# usomiq.net
KiCad netlist of a schematic drawn in Altium Designer
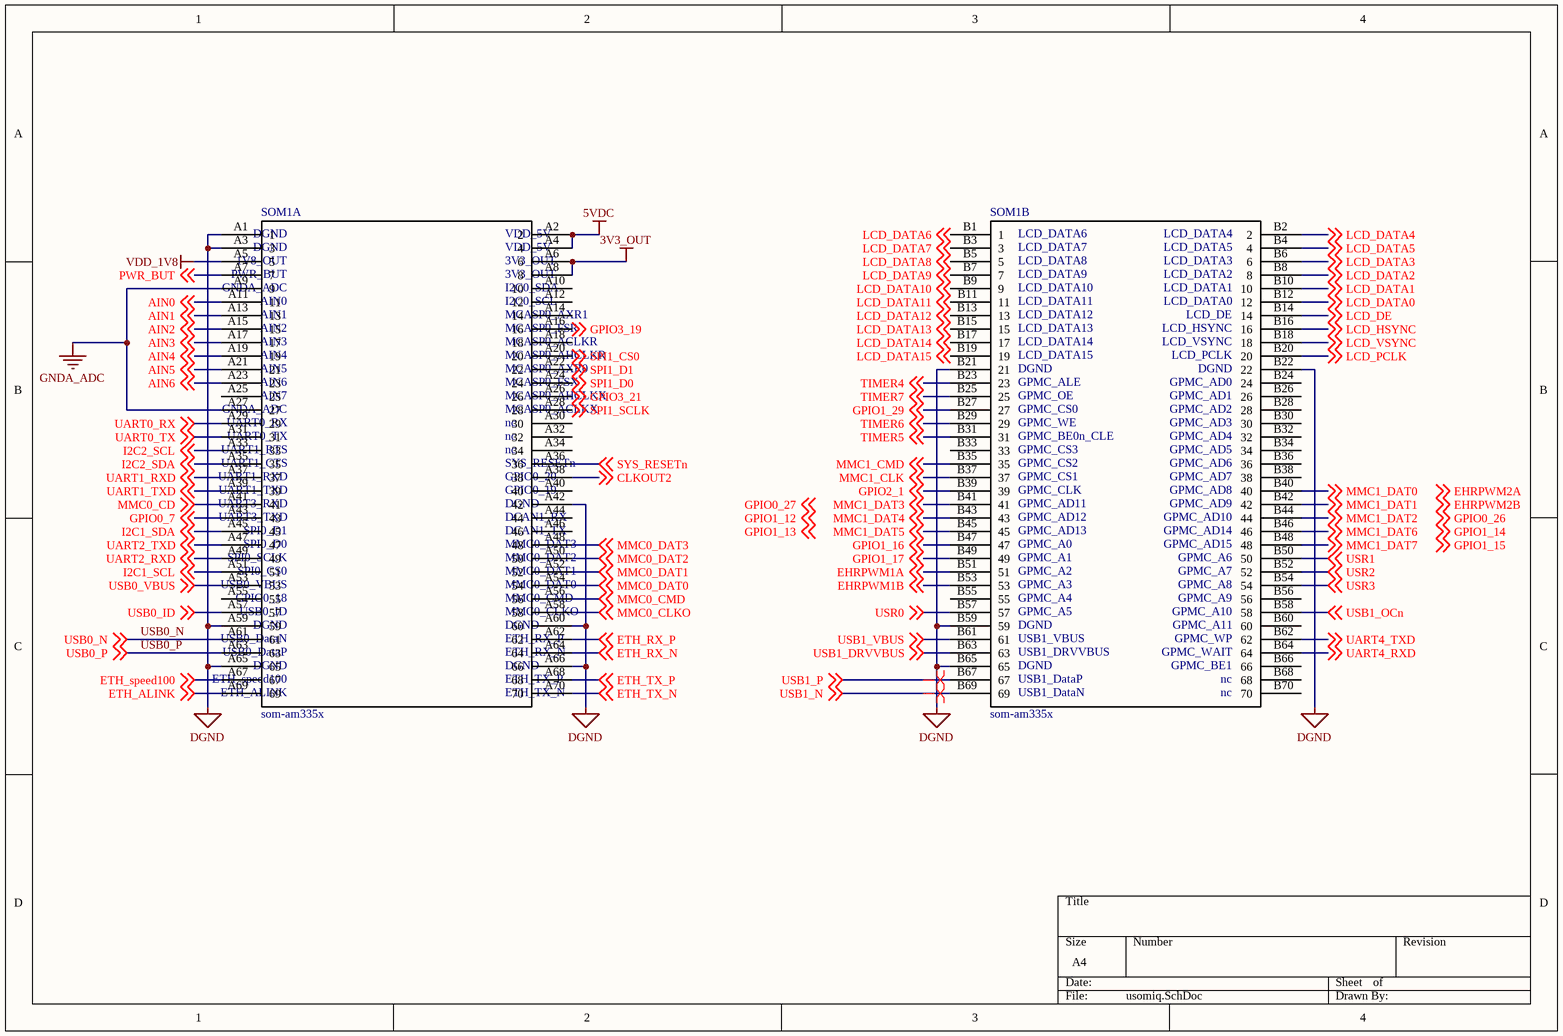
[diagram p0: usomiq.SchDoc]

(export (version "E")
  (design (tool "Eeschema 10.0.6"))
  (components
    (comp (ref "SOM1")
      (value "som-am335x")
      (footprint "am3359_module-sockets")
      (libsource (lib "usomiq-base") (part "som-am335x"))
    )
  )
  (nets
    (net (code "1") (name "3V3_OUT") (class "Default")
      (node (ref "SOM1") (pin "A6") (pinfunction "6_A6") (pintype "passive"))
      (node (ref "SOM1") (pin "A8") (pinfunction "8_A8") (pintype "passive"))
    )
    (net (code "2") (name "5VDC") (class "Default")
      (node (ref "SOM1") (pin "A2") (pinfunction "2_A2") (pintype "passive"))
      (node (ref "SOM1") (pin "A4") (pinfunction "4_A4") (pintype "passive"))
    )
    (net (code "3") (name "AIN0") (class "Default")
      (node (ref "SOM1") (pin "A11") (pinfunction "11_A11") (pintype "passive"))
    )
    (net (code "4") (name "AIN1") (class "Default")
      (node (ref "SOM1") (pin "A13") (pinfunction "13_A13") (pintype "passive"))
    )
    (net (code "5") (name "AIN2") (class "Default")
      (node (ref "SOM1") (pin "A15") (pinfunction "15_A15") (pintype "passive"))
    )
    (net (code "6") (name "AIN3") (class "Default")
      (node (ref "SOM1") (pin "A17") (pinfunction "17_A17") (pintype "passive"))
    )
    (net (code "7") (name "AIN4") (class "Default")
      (node (ref "SOM1") (pin "A19") (pinfunction "19_A19") (pintype "passive"))
    )
    (net (code "8") (name "AIN5") (class "Default")
      (node (ref "SOM1") (pin "A21") (pinfunction "21_A21") (pintype "passive"))
    )
    (net (code "9") (name "AIN6") (class "Default")
      (node (ref "SOM1") (pin "A23") (pinfunction "23_A23") (pintype "passive"))
    )
    (net (code "10") (name "CLKOUT2") (class "Default")
      (node (ref "SOM1") (pin "A38") (pinfunction "38_A38") (pintype "passive"))
    )
    (net (code "11") (name "DGND") (class "Default")
      (node (ref "SOM1") (pin "A1") (pinfunction "1_A1") (pintype "passive"))
      (node (ref "SOM1") (pin "A3") (pinfunction "3_A3") (pintype "passive"))
      (node (ref "SOM1") (pin "A42") (pinfunction "42_A42") (pintype "passive"))
      (node (ref "SOM1") (pin "A59") (pinfunction "59_A59") (pintype "passive"))
      (node (ref "SOM1") (pin "A60") (pinfunction "60_A60") (pintype "passive"))
      (node (ref "SOM1") (pin "A65") (pinfunction "65_A65") (pintype "passive"))
      (node (ref "SOM1") (pin "A66") (pinfunction "66_A66") (pintype "passive"))
      (node (ref "SOM1") (pin "B21") (pinfunction "21_B21") (pintype "passive"))
      (node (ref "SOM1") (pin "B22") (pinfunction "22_B22") (pintype "passive"))
      (node (ref "SOM1") (pin "B59") (pinfunction "59_B59") (pintype "passive"))
      (node (ref "SOM1") (pin "B65") (pinfunction "65_B65") (pintype "passive"))
    )
    (net (code "12") (name "EHRPWM1A") (class "Default")
      (node (ref "SOM1") (pin "B51") (pinfunction "51_B51") (pintype "passive"))
    )
    (net (code "13") (name "EHRPWM1B") (class "Default")
      (node (ref "SOM1") (pin "B53") (pinfunction "53_B53") (pintype "passive"))
    )
    (net (code "16") (name "ETH_ALINK") (class "Default")
      (node (ref "SOM1") (pin "A69") (pinfunction "69_A69") (pintype "passive"))
    )
    (net (code "17") (name "ETH_RX_N") (class "Default")
      (node (ref "SOM1") (pin "A64") (pinfunction "64_A64") (pintype "passive"))
    )
    (net (code "18") (name "ETH_RX_P") (class "Default")
      (node (ref "SOM1") (pin "A62") (pinfunction "62_A62") (pintype "passive"))
    )
    (net (code "19") (name "ETH_TX_N") (class "Default")
      (node (ref "SOM1") (pin "A70") (pinfunction "70_A70") (pintype "passive"))
    )
    (net (code "20") (name "ETH_TX_P") (class "Default")
      (node (ref "SOM1") (pin "A68") (pinfunction "68_A68") (pintype "passive"))
    )
    (net (code "21") (name "ETH_speed100") (class "Default")
      (node (ref "SOM1") (pin "A67") (pinfunction "67_A67") (pintype "passive"))
    )
    (net (code "22") (name "GNDA_ADC") (class "Default")
      (node (ref "SOM1") (pin "A27") (pinfunction "27_A27") (pintype "passive"))
      (node (ref "SOM1") (pin "A9") (pinfunction "9_A9") (pintype "passive"))
    )
    (net (code "23") (name "GPIO0_7") (class "Default")
      (node (ref "SOM1") (pin "A43") (pinfunction "43_A43") (pintype "passive"))
    )
    (net (code "30") (name "GPIO1_16") (class "Default")
      (node (ref "SOM1") (pin "B47") (pinfunction "47_B47") (pintype "passive"))
    )
    (net (code "31") (name "GPIO1_17") (class "Default")
      (node (ref "SOM1") (pin "B49") (pinfunction "49_B49") (pintype "passive"))
    )
    (net (code "32") (name "GPIO1_29") (class "Default")
      (node (ref "SOM1") (pin "B27") (pinfunction "27_B27") (pintype "passive"))
    )
    (net (code "33") (name "GPIO2_1") (class "Default")
      (node (ref "SOM1") (pin "B39") (pinfunction "39_B39") (pintype "passive"))
    )
    (net (code "34") (name "GPIO3_19") (class "Default")
      (node (ref "SOM1") (pin "A16") (pinfunction "16_A16") (pintype "passive"))
    )
    (net (code "35") (name "GPIO3_21") (class "Default")
      (node (ref "SOM1") (pin "A26") (pinfunction "26_A26") (pintype "passive"))
    )
    (net (code "36") (name "I2C1_SCL") (class "Default")
      (node (ref "SOM1") (pin "A51") (pinfunction "51_A51") (pintype "passive"))
    )
    (net (code "37") (name "I2C1_SDA") (class "Default")
      (node (ref "SOM1") (pin "A45") (pinfunction "45_A45") (pintype "passive"))
    )
    (net (code "38") (name "I2C2_SCL") (class "Default")
      (node (ref "SOM1") (pin "A33") (pinfunction "33_A33") (pintype "passive"))
    )
    (net (code "39") (name "I2C2_SDA") (class "Default")
      (node (ref "SOM1") (pin "A35") (pinfunction "35_A35") (pintype "passive"))
    )
    (net (code "40") (name "LCD_DATA0") (class "Default")
      (node (ref "SOM1") (pin "B12") (pinfunction "12_B12") (pintype "passive"))
    )
    (net (code "41") (name "LCD_DATA1") (class "Default")
      (node (ref "SOM1") (pin "B10") (pinfunction "10_B10") (pintype "passive"))
    )
    (net (code "42") (name "LCD_DATA2") (class "Default")
      (node (ref "SOM1") (pin "B8") (pinfunction "8_B8") (pintype "passive"))
    )
    (net (code "43") (name "LCD_DATA3") (class "Default")
      (node (ref "SOM1") (pin "B6") (pinfunction "6_B6") (pintype "passive"))
    )
    (net (code "44") (name "LCD_DATA4") (class "Default")
      (node (ref "SOM1") (pin "B2") (pinfunction "2_B2") (pintype "passive"))
    )
    (net (code "45") (name "LCD_DATA5") (class "Default")
      (node (ref "SOM1") (pin "B4") (pinfunction "4_B4") (pintype "passive"))
    )
    (net (code "46") (name "LCD_DATA6") (class "Default")
      (node (ref "SOM1") (pin "B1") (pinfunction "1_B1") (pintype "passive"))
    )
    (net (code "47") (name "LCD_DATA7") (class "Default")
      (node (ref "SOM1") (pin "B3") (pinfunction "3_B3") (pintype "passive"))
    )
    (net (code "48") (name "LCD_DATA8") (class "Default")
      (node (ref "SOM1") (pin "B5") (pinfunction "5_B5") (pintype "passive"))
    )
    (net (code "49") (name "LCD_DATA9") (class "Default")
      (node (ref "SOM1") (pin "B7") (pinfunction "7_B7") (pintype "passive"))
    )
    (net (code "50") (name "LCD_DATA10") (class "Default")
      (node (ref "SOM1") (pin "B9") (pinfunction "9_B9") (pintype "passive"))
    )
    (net (code "51") (name "LCD_DATA11") (class "Default")
      (node (ref "SOM1") (pin "B11") (pinfunction "11_B11") (pintype "passive"))
    )
    (net (code "52") (name "LCD_DATA12") (class "Default")
      (node (ref "SOM1") (pin "B13") (pinfunction "13_B13") (pintype "passive"))
    )
    (net (code "53") (name "LCD_DATA13") (class "Default")
      (node (ref "SOM1") (pin "B15") (pinfunction "15_B15") (pintype "passive"))
    )
    (net (code "54") (name "LCD_DATA14") (class "Default")
      (node (ref "SOM1") (pin "B17") (pinfunction "17_B17") (pintype "passive"))
    )
    (net (code "55") (name "LCD_DATA15") (class "Default")
      (node (ref "SOM1") (pin "B19") (pinfunction "19_B19") (pintype "passive"))
    )
    (net (code "56") (name "LCD_DE") (class "Default")
      (node (ref "SOM1") (pin "B14") (pinfunction "14_B14") (pintype "passive"))
    )
    (net (code "57") (name "LCD_HSYNC") (class "Default")
      (node (ref "SOM1") (pin "B16") (pinfunction "16_B16") (pintype "passive"))
    )
    (net (code "58") (name "LCD_PCLK") (class "Default")
      (node (ref "SOM1") (pin "B20") (pinfunction "20_B20") (pintype "passive"))
    )
    (net (code "59") (name "LCD_VSYNC") (class "Default")
      (node (ref "SOM1") (pin "B18") (pinfunction "18_B18") (pintype "passive"))
    )
    (net (code "60") (name "MMC0_CD") (class "Default")
      (node (ref "SOM1") (pin "A41") (pinfunction "41_A41") (pintype "passive"))
    )
    (net (code "61") (name "MMC0_CLKO") (class "Default")
      (node (ref "SOM1") (pin "A58") (pinfunction "58_A58") (pintype "passive"))
    )
    (net (code "62") (name "MMC0_CMD") (class "Default")
      (node (ref "SOM1") (pin "A56") (pinfunction "56_A56") (pintype "passive"))
    )
    (net (code "63") (name "MMC0_DAT0") (class "Default")
      (node (ref "SOM1") (pin "A54") (pinfunction "54_A54") (pintype "passive"))
    )
    (net (code "64") (name "MMC0_DAT1") (class "Default")
      (node (ref "SOM1") (pin "A52") (pinfunction "52_A52") (pintype "passive"))
    )
    (net (code "65") (name "MMC0_DAT2") (class "Default")
      (node (ref "SOM1") (pin "A50") (pinfunction "50_A50") (pintype "passive"))
    )
    (net (code "66") (name "MMC0_DAT3") (class "Default")
      (node (ref "SOM1") (pin "A48") (pinfunction "48_A48") (pintype "passive"))
    )
    (net (code "67") (name "MMC1_CLK") (class "Default")
      (node (ref "SOM1") (pin "B37") (pinfunction "37_B37") (pintype "passive"))
    )
    (net (code "68") (name "MMC1_CMD") (class "Default")
      (node (ref "SOM1") (pin "B35") (pinfunction "35_B35") (pintype "passive"))
    )
    (net (code "69") (name "MMC1_DAT0") (class "Default")
      (node (ref "SOM1") (pin "B40") (pinfunction "40_B40") (pintype "passive"))
    )
    (net (code "70") (name "MMC1_DAT1") (class "Default")
      (node (ref "SOM1") (pin "B42") (pinfunction "42_B42") (pintype "passive"))
    )
    (net (code "71") (name "MMC1_DAT2") (class "Default")
      (node (ref "SOM1") (pin "B44") (pinfunction "44_B44") (pintype "passive"))
    )
    (net (code "72") (name "MMC1_DAT3") (class "Default")
      (node (ref "SOM1") (pin "B41") (pinfunction "41_B41") (pintype "passive"))
    )
    (net (code "73") (name "MMC1_DAT4") (class "Default")
      (node (ref "SOM1") (pin "B43") (pinfunction "43_B43") (pintype "passive"))
    )
    (net (code "74") (name "MMC1_DAT5") (class "Default")
      (node (ref "SOM1") (pin "B45") (pinfunction "45_B45") (pintype "passive"))
    )
    (net (code "75") (name "MMC1_DAT6") (class "Default")
      (node (ref "SOM1") (pin "B46") (pinfunction "46_B46") (pintype "passive"))
    )
    (net (code "76") (name "MMC1_DAT7") (class "Default")
      (node (ref "SOM1") (pin "B48") (pinfunction "48_B48") (pintype "passive"))
    )
    (net (code "77") (name "PWR_BUT") (class "Default")
      (node (ref "SOM1") (pin "A7") (pinfunction "7_A7") (pintype "passive"))
    )
    (net (code "78") (name "SPI1_CS0") (class "Default")
      (node (ref "SOM1") (pin "A20") (pinfunction "20_A20") (pintype "passive"))
    )
    (net (code "79") (name "SPI1_D0") (class "Default")
      (node (ref "SOM1") (pin "A24") (pinfunction "24_A24") (pintype "passive"))
    )
    (net (code "80") (name "SPI1_D1") (class "Default")
      (node (ref "SOM1") (pin "A22") (pinfunction "22_A22") (pintype "passive"))
    )
    (net (code "81") (name "SPI1_SCLK") (class "Default")
      (node (ref "SOM1") (pin "A28") (pinfunction "28_A28") (pintype "passive"))
    )
    (net (code "82") (name "SYS_RESETn") (class "Default")
      (node (ref "SOM1") (pin "A36") (pinfunction "36_A36") (pintype "passive"))
    )
    (net (code "83") (name "TIMER4") (class "Default")
      (node (ref "SOM1") (pin "B23") (pinfunction "23_B23") (pintype "passive"))
    )
    (net (code "84") (name "TIMER5") (class "Default")
      (node (ref "SOM1") (pin "B31") (pinfunction "31_B31") (pintype "passive"))
    )
    (net (code "85") (name "TIMER6") (class "Default")
      (node (ref "SOM1") (pin "B29") (pinfunction "29_B29") (pintype "passive"))
    )
    (net (code "86") (name "TIMER7") (class "Default")
      (node (ref "SOM1") (pin "B25") (pinfunction "25_B25") (pintype "passive"))
    )
    (net (code "87") (name "UART0_RX") (class "Default")
      (node (ref "SOM1") (pin "A29") (pinfunction "29_A29") (pintype "passive"))
    )
    (net (code "88") (name "UART0_TX") (class "Default")
      (node (ref "SOM1") (pin "A31") (pinfunction "31_A31") (pintype "passive"))
    )
    (net (code "89") (name "UART1_RXD") (class "Default")
      (node (ref "SOM1") (pin "A37") (pinfunction "37_A37") (pintype "passive"))
    )
    (net (code "90") (name "UART1_TXD") (class "Default")
      (node (ref "SOM1") (pin "A39") (pinfunction "39_A39") (pintype "passive"))
    )
    (net (code "91") (name "UART2_RXD") (class "Default")
      (node (ref "SOM1") (pin "A49") (pinfunction "49_A49") (pintype "passive"))
    )
    (net (code "92") (name "UART2_TXD") (class "Default")
      (node (ref "SOM1") (pin "A47") (pinfunction "47_A47") (pintype "passive"))
    )
    (net (code "93") (name "UART4_RXD") (class "Default")
      (node (ref "SOM1") (pin "B64") (pinfunction "64_B64") (pintype "passive"))
    )
    (net (code "94") (name "UART4_TXD") (class "Default")
      (node (ref "SOM1") (pin "B62") (pinfunction "62_B62") (pintype "passive"))
    )
    (net (code "95") (name "USB0_ID") (class "Default")
      (node (ref "SOM1") (pin "A57") (pinfunction "57_A57") (pintype "passive"))
    )
    (net (code "96") (name "USB0_N") (class "Default")
      (node (ref "SOM1") (pin "A61") (pinfunction "61_A61") (pintype "passive"))
    )
    (net (code "97") (name "USB0_P") (class "Default")
      (node (ref "SOM1") (pin "A63") (pinfunction "63_A63") (pintype "passive"))
    )
    (net (code "98") (name "USB0_VBUS") (class "Default")
      (node (ref "SOM1") (pin "A53") (pinfunction "53_A53") (pintype "passive"))
    )
    (net (code "99") (name "USB1_DRVVBUS") (class "Default")
      (node (ref "SOM1") (pin "B63") (pinfunction "63_B63") (pintype "passive"))
    )
    (net (code "100") (name "USB1_N") (class "Default")
      (node (ref "SOM1") (pin "B69") (pinfunction "69_B69") (pintype "passive"))
    )
    (net (code "101") (name "USB1_OCn") (class "Default")
      (node (ref "SOM1") (pin "B58") (pinfunction "58_B58") (pintype "passive"))
    )
    (net (code "102") (name "USB1_P") (class "Default")
      (node (ref "SOM1") (pin "B67") (pinfunction "67_B67") (pintype "passive"))
    )
    (net (code "103") (name "USB1_VBUS") (class "Default")
      (node (ref "SOM1") (pin "B61") (pinfunction "61_B61") (pintype "passive"))
    )
    (net (code "104") (name "USR0") (class "Default")
      (node (ref "SOM1") (pin "B57") (pinfunction "57_B57") (pintype "passive"))
    )
    (net (code "105") (name "USR1") (class "Default")
      (node (ref "SOM1") (pin "B50") (pinfunction "50_B50") (pintype "passive"))
    )
    (net (code "106") (name "USR2") (class "Default")
      (node (ref "SOM1") (pin "B52") (pinfunction "52_B52") (pintype "passive"))
    )
    (net (code "107") (name "USR3") (class "Default")
      (node (ref "SOM1") (pin "B54") (pinfunction "54_B54") (pintype "passive"))
    )
    (net (code "108") (name "VDD_1V8") (class "Default")
      (node (ref "SOM1") (pin "A5") (pinfunction "5_A5") (pintype "passive"))
    )
    (net (code "109") (name "unconnected-(SOM1A-10-PadA10)") (class "Default")
      (node (ref "SOM1") (pin "A10") (pinfunction "10_A10") (pintype "passive"))
    )
    (net (code "110") (name "unconnected-(SOM1A-12-PadA12)") (class "Default")
      (node (ref "SOM1") (pin "A12") (pinfunction "12_A12") (pintype "passive"))
    )
    (net (code "111") (name "unconnected-(SOM1A-14-PadA14)") (class "Default")
      (node (ref "SOM1") (pin "A14") (pinfunction "14_A14") (pintype "passive"))
    )
    (net (code "112") (name "unconnected-(SOM1A-18-PadA18)") (class "Default")
      (node (ref "SOM1") (pin "A18") (pinfunction "18_A18") (pintype "passive"))
    )
    (net (code "113") (name "unconnected-(SOM1A-25-PadA25)") (class "Default")
      (node (ref "SOM1") (pin "A25") (pinfunction "25_A25") (pintype "passive"))
    )
    (net (code "114") (name "unconnected-(SOM1A-30-PadA30)") (class "Default")
      (node (ref "SOM1") (pin "A30") (pinfunction "30_A30") (pintype "passive"))
    )
    (net (code "115") (name "unconnected-(SOM1A-32-PadA32)") (class "Default")
      (node (ref "SOM1") (pin "A32") (pinfunction "32_A32") (pintype "passive"))
    )
    (net (code "116") (name "unconnected-(SOM1A-34-PadA34)") (class "Default")
      (node (ref "SOM1") (pin "A34") (pinfunction "34_A34") (pintype "passive"))
    )
    (net (code "117") (name "unconnected-(SOM1A-40-PadA40)") (class "Default")
      (node (ref "SOM1") (pin "A40") (pinfunction "40_A40") (pintype "passive"))
    )
    (net (code "118") (name "unconnected-(SOM1A-44-PadA44)") (class "Default")
      (node (ref "SOM1") (pin "A44") (pinfunction "44_A44") (pintype "passive"))
    )
    (net (code "119") (name "unconnected-(SOM1A-46-PadA46)") (class "Default")
      (node (ref "SOM1") (pin "A46") (pinfunction "46_A46") (pintype "passive"))
    )
    (net (code "120") (name "unconnected-(SOM1A-55-PadA55)") (class "Default")
      (node (ref "SOM1") (pin "A55") (pinfunction "55_A55") (pintype "passive"))
    )
    (net (code "121") (name "unconnected-(SOM1B-24-PadB24)") (class "Default")
      (node (ref "SOM1") (pin "B24") (pinfunction "24_B24") (pintype "passive"))
    )
    (net (code "122") (name "unconnected-(SOM1B-26-PadB26)") (class "Default")
      (node (ref "SOM1") (pin "B26") (pinfunction "26_B26") (pintype "passive"))
    )
    (net (code "123") (name "unconnected-(SOM1B-28-PadB28)") (class "Default")
      (node (ref "SOM1") (pin "B28") (pinfunction "28_B28") (pintype "passive"))
    )
    (net (code "124") (name "unconnected-(SOM1B-30-PadB30)") (class "Default")
      (node (ref "SOM1") (pin "B30") (pinfunction "30_B30") (pintype "passive"))
    )
    (net (code "125") (name "unconnected-(SOM1B-32-PadB32)") (class "Default")
      (node (ref "SOM1") (pin "B32") (pinfunction "32_B32") (pintype "passive"))
    )
    (net (code "126") (name "unconnected-(SOM1B-33-PadB33)") (class "Default")
      (node (ref "SOM1") (pin "B33") (pinfunction "33_B33") (pintype "passive"))
    )
    (net (code "127") (name "unconnected-(SOM1B-34-PadB34)") (class "Default")
      (node (ref "SOM1") (pin "B34") (pinfunction "34_B34") (pintype "passive"))
    )
    (net (code "128") (name "unconnected-(SOM1B-36-PadB36)") (class "Default")
      (node (ref "SOM1") (pin "B36") (pinfunction "36_B36") (pintype "passive"))
    )
    (net (code "129") (name "unconnected-(SOM1B-38-PadB38)") (class "Default")
      (node (ref "SOM1") (pin "B38") (pinfunction "38_B38") (pintype "passive"))
    )
    (net (code "130") (name "unconnected-(SOM1B-55-PadB55)") (class "Default")
      (node (ref "SOM1") (pin "B55") (pinfunction "55_B55") (pintype "passive"))
    )
    (net (code "131") (name "unconnected-(SOM1B-56-PadB56)") (class "Default")
      (node (ref "SOM1") (pin "B56") (pinfunction "56_B56") (pintype "passive"))
    )
    (net (code "132") (name "unconnected-(SOM1B-60-PadB60)") (class "Default")
      (node (ref "SOM1") (pin "B60") (pinfunction "60_B60") (pintype "passive"))
    )
    (net (code "133") (name "unconnected-(SOM1B-66-PadB66)") (class "Default")
      (node (ref "SOM1") (pin "B66") (pinfunction "66_B66") (pintype "passive"))
    )
    (net (code "134") (name "unconnected-(SOM1B-68-PadB68)") (class "Default")
      (node (ref "SOM1") (pin "B68") (pinfunction "68_B68") (pintype "passive"))
    )
    (net (code "135") (name "unconnected-(SOM1B-70-PadB70)") (class "Default")
      (node (ref "SOM1") (pin "B70") (pinfunction "70_B70") (pintype "passive"))
    )
  )
)
